# MO1.net
KiCad netlist of a schematic drawn in EAGLE
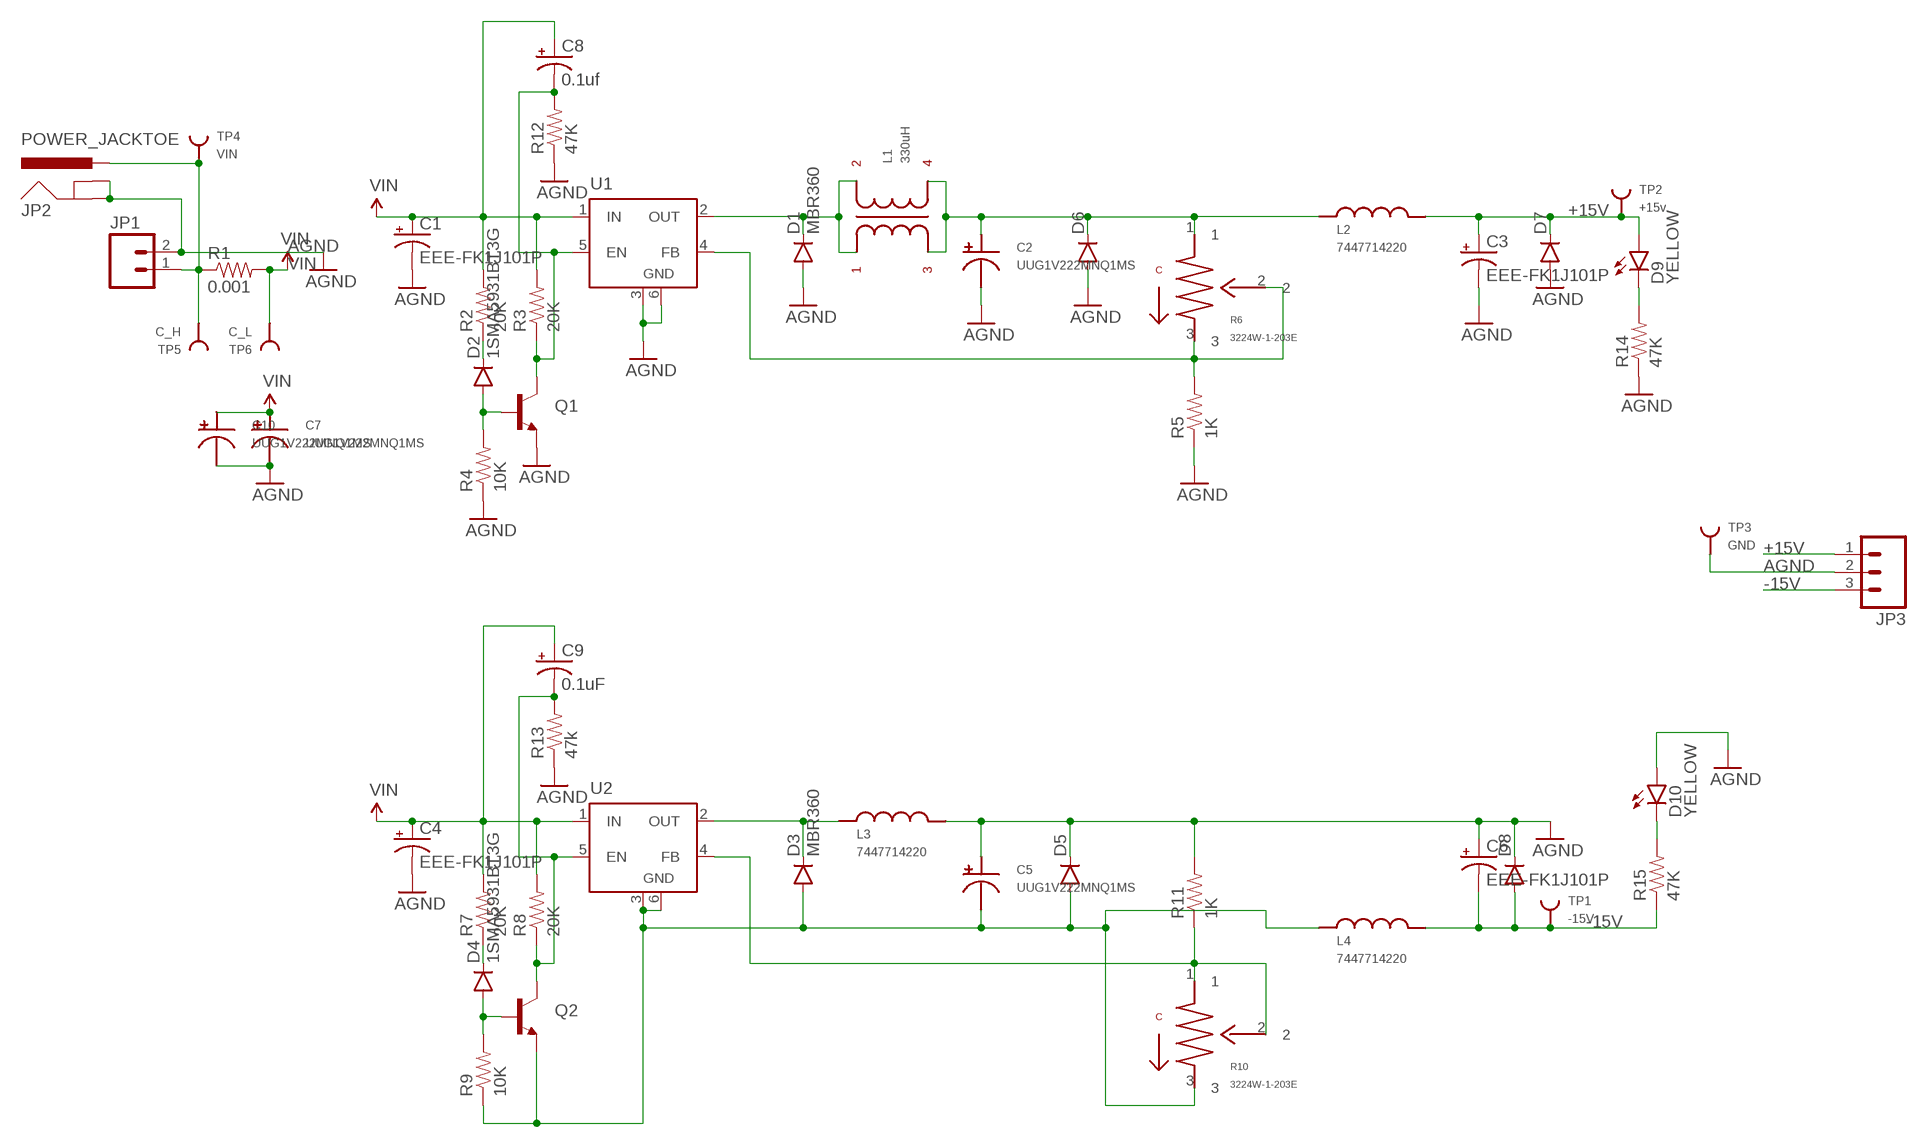
[diagram p0: schematic, sheet 1]

(export (version "E")
  (design (tool "Eeschema 10.0.6"))
  (components
    (comp (ref "C1")
      (value "EEE-FK1J101P")
      (footprint "eagle-import:PANASONIC_G")
      (libsource (lib "eagle-import") (part "CAP_POLG"))
    )
    (comp (ref "C2")
      (value "UUG1V222MNQ1MS")
      (footprint "eagle-import:POL_18X21.5")
      (libsource (lib "eagle-import") (part "UUG1V222MNQ1MS"))
    )
    (comp (ref "C3")
      (value "EEE-FK1J101P")
      (footprint "eagle-import:PANASONIC_G")
      (libsource (lib "eagle-import") (part "CAP_POLG"))
    )
    (comp (ref "C4")
      (value "EEE-FK1J101P")
      (footprint "eagle-import:PANASONIC_G")
      (libsource (lib "eagle-import") (part "CAP_POLG"))
    )
    (comp (ref "C5")
      (value "UUG1V222MNQ1MS")
      (footprint "eagle-import:POL_18X21.5")
      (libsource (lib "eagle-import") (part "UUG1V222MNQ1MS"))
    )
    (comp (ref "C6")
      (value "EEE-FK1J101P")
      (footprint "eagle-import:PANASONIC_G")
      (libsource (lib "eagle-import") (part "CAP_POLG"))
    )
    (comp (ref "C7")
      (value "UUG1V222MNQ1MS")
      (footprint "eagle-import:POL_18X21.5")
      (libsource (lib "eagle-import") (part "UUG1V222MNQ1MS"))
    )
    (comp (ref "C8")
      (value "0.1uf")
      (footprint "eagle-import:PANASONIC_C")
      (libsource (lib "eagle-import") (part "CAP_POLC"))
    )
    (comp (ref "C9")
      (value "0.1uF")
      (footprint "eagle-import:PANASONIC_C")
      (libsource (lib "eagle-import") (part "CAP_POLC"))
    )
    (comp (ref "C10")
      (value "UUG1V222MNQ1MS")
      (footprint "eagle-import:POL_18X21.5")
      (libsource (lib "eagle-import") (part "UUG1V222MNQ1MS"))
    )
    (comp (ref "D1")
      (value "MBR360")
      (footprint "eagle-import:SMB-DIODE")
      (libsource (lib "eagle-import") (part "DIODESMB"))
    )
    (comp (ref "D2")
      (value "1SMA5931BT3G")
      (footprint "eagle-import:SMA-DIODE")
      (libsource (lib "eagle-import") (part "DIODESMA"))
    )
    (comp (ref "D3")
      (value "MBR360")
      (footprint "eagle-import:SMB-DIODE")
      (libsource (lib "eagle-import") (part "DIODESMB"))
    )
    (comp (ref "D4")
      (value "1SMA5931BT3G")
      (footprint "eagle-import:SMA-DIODE")
      (libsource (lib "eagle-import") (part "DIODESMA"))
    )
    (comp (ref "D5")
      (value "DIODESMA")
      (footprint "eagle-import:SMA-DIODE")
      (libsource (lib "eagle-import") (part "DIODESMA"))
    )
    (comp (ref "D6")
      (value "DIODESMA")
      (footprint "eagle-import:SMA-DIODE")
      (libsource (lib "eagle-import") (part "DIODESMA"))
    )
    (comp (ref "D7")
      (value "DIODESMA")
      (footprint "eagle-import:SMA-DIODE")
      (libsource (lib "eagle-import") (part "DIODESMA"))
    )
    (comp (ref "D8")
      (value "DIODESMA")
      (footprint "eagle-import:SMA-DIODE")
      (libsource (lib "eagle-import") (part "DIODESMA"))
    )
    (comp (ref "D9")
      (value "YELLOW")
      (footprint "eagle-import:LED-1206")
      (libsource (lib "eagle-import") (part "LED-YELLOW1206"))
    )
    (comp (ref "D10")
      (value "YELLOW")
      (footprint "eagle-import:LED-1206")
      (libsource (lib "eagle-import") (part "LED-YELLOW1206"))
    )
    (comp (ref "JP1")
      (value "M023.5MM_LOCK")
      (footprint "eagle-import:SCREWTERMINAL-3.5MM-2_LOCK")
      (libsource (lib "eagle-import") (part "M023.5MM_LOCK"))
    )
    (comp (ref "JP2")
      (value "POWER_JACKTOE")
      (footprint "eagle-import:POWER_JACK_SMD_OVERPASTE_TOE")
      (libsource (lib "eagle-import") (part "POWER_JACKTOE"))
    )
    (comp (ref "JP3")
      (value "M03SCREW_LOCK")
      (footprint "eagle-import:SCREWTERMINAL-3.5MM-3_LOCK.007S")
      (libsource (lib "eagle-import") (part "M03SCREW_LOCK"))
    )
    (comp (ref "L1")
      (value "330uH")
      (footprint "eagle-import:DRQ127")
      (libsource (lib "eagle-import") (part "DRQ127-331-R"))
    )
    (comp (ref "L2")
      (value "7447714220")
      (footprint "eagle-import:INDUCTOR_10X10")
      (libsource (lib "eagle-import") (part "7447714220"))
    )
    (comp (ref "L3")
      (value "7447714220")
      (footprint "eagle-import:INDUCTOR_10X10")
      (libsource (lib "eagle-import") (part "7447714220"))
    )
    (comp (ref "L4")
      (value "7447714220")
      (footprint "eagle-import:INDUCTOR_10X10")
      (libsource (lib "eagle-import") (part "7447714220"))
    )
    (comp (ref "Q1")
      (value "TRANSISTOR_NPNSOT23-3")
      (footprint "eagle-import:SOT23-3")
      (libsource (lib "eagle-import") (part "TRANSISTOR_NPNSOT23-3"))
    )
    (comp (ref "Q2")
      (value "TRANSISTOR_NPNSOT23-3")
      (footprint "eagle-import:SOT23-3")
      (libsource (lib "eagle-import") (part "TRANSISTOR_NPNSOT23-3"))
    )
    (comp (ref "R1")
      (value "0.001")
      (footprint "eagle-import:2512")
      (libsource (lib "eagle-import") (part "0.001OHM-3W-1%(2512)3W/1%"))
    )
    (comp (ref "R2")
      (value "20K")
      (footprint "eagle-import:0603-RES")
      (libsource (lib "eagle-import") (part "1.8KOHM1/10W1%(0603)"))
    )
    (comp (ref "R3")
      (value "20K")
      (footprint "eagle-import:0603-RES")
      (libsource (lib "eagle-import") (part "1.8KOHM1/10W1%(0603)"))
    )
    (comp (ref "R4")
      (value "10K")
      (footprint "eagle-import:0603-RES")
      (libsource (lib "eagle-import") (part "1.8KOHM1/10W1%(0603)"))
    )
    (comp (ref "R5")
      (value "1K")
      (footprint "eagle-import:0805")
      (libsource (lib "eagle-import") (part "0.75OHM-1/4W-1%(0805)"))
    )
    (comp (ref "R6")
      (value "3224W-1-203E")
      (footprint "eagle-import:3224W")
      (libsource (lib "eagle-import") (part "3224W-1-203E"))
    )
    (comp (ref "R7")
      (value "20K")
      (footprint "eagle-import:0603-RES")
      (libsource (lib "eagle-import") (part "1.8KOHM1/10W1%(0603)"))
    )
    (comp (ref "R8")
      (value "20K")
      (footprint "eagle-import:0603-RES")
      (libsource (lib "eagle-import") (part "1.8KOHM1/10W1%(0603)"))
    )
    (comp (ref "R9")
      (value "10K")
      (footprint "eagle-import:0603-RES")
      (libsource (lib "eagle-import") (part "1.8KOHM1/10W1%(0603)"))
    )
    (comp (ref "R10")
      (value "3224W-1-203E")
      (footprint "eagle-import:3224W")
      (libsource (lib "eagle-import") (part "3224W-1-203E"))
    )
    (comp (ref "R11")
      (value "1K")
      (footprint "eagle-import:0805")
      (libsource (lib "eagle-import") (part "0.75OHM-1/4W-1%(0805)"))
    )
    (comp (ref "R12")
      (value "47K")
      (footprint "eagle-import:0603-RES")
      (libsource (lib "eagle-import") (part "1.8KOHM1/10W1%(0603)"))
    )
    (comp (ref "R13")
      (value "47k")
      (footprint "eagle-import:0603-RES")
      (libsource (lib "eagle-import") (part "1.8KOHM1/10W1%(0603)"))
    )
    (comp (ref "R14")
      (value "47K")
      (footprint "eagle-import:0603-RES")
      (libsource (lib "eagle-import") (part "1.8KOHM1/10W1%(0603)"))
    )
    (comp (ref "R15")
      (value "47K")
      (footprint "eagle-import:0603-RES")
      (libsource (lib "eagle-import") (part "1.8KOHM1/10W1%(0603)"))
    )
    (comp (ref "TP1")
      (value "-15V")
      (footprint "eagle-import:TP")
      (libsource (lib "eagle-import") (part "TP"))
    )
    (comp (ref "TP2")
      (value "+15v")
      (footprint "eagle-import:TP")
      (libsource (lib "eagle-import") (part "TP"))
    )
    (comp (ref "TP3")
      (value "GND")
      (footprint "eagle-import:TP")
      (libsource (lib "eagle-import") (part "TP"))
    )
    (comp (ref "TP4")
      (value "VIN")
      (footprint "eagle-import:TP")
      (libsource (lib "eagle-import") (part "TP"))
    )
    (comp (ref "TP5")
      (value "C_H")
      (footprint "eagle-import:TP")
      (libsource (lib "eagle-import") (part "TP"))
    )
    (comp (ref "TP6")
      (value "C_L")
      (footprint "eagle-import:TP")
      (libsource (lib "eagle-import") (part "TP"))
    )
    (comp (ref "U1")
      (value "LM2596S")
      (footprint "eagle-import:TO263-5")
      (libsource (lib "eagle-import") (part "LM2596S"))
    )
    (comp (ref "U2")
      (value "LM2596S")
      (footprint "eagle-import:TO263-5")
      (libsource (lib "eagle-import") (part "LM2596S"))
    )
  )
  (nets
    (net (code "1") (name "/+15V") (class "Default")
      (node (ref "C3") (pin "+") (pinfunction "+_+") (pintype "passive"))
      (node (ref "D7") (pin "C") (pinfunction "C_C") (pintype "passive"))
      (node (ref "D9") (pin "A") (pinfunction "A_A") (pintype "passive"))
      (node (ref "JP3") (pin "1") (pinfunction "1_1") (pintype "passive"))
      (node (ref "L2") (pin "2") (pinfunction "2_2") (pintype "bidirectional"))
      (node (ref "TP2") (pin "P$1") (pinfunction "TP_P$1") (pintype "bidirectional"))
    )
    (net (code "2") (name "/-15V") (class "Default")
      (node (ref "C6") (pin "-") (pinfunction "-_-") (pintype "passive"))
      (node (ref "D8") (pin "A") (pinfunction "A_A") (pintype "passive"))
      (node (ref "JP3") (pin "3") (pinfunction "3_3") (pintype "passive"))
      (node (ref "L4") (pin "2") (pinfunction "2_2") (pintype "bidirectional"))
      (node (ref "R15") (pin "1") (pinfunction "1_1") (pintype "passive"))
      (node (ref "TP1") (pin "P$1") (pinfunction "TP_P$1") (pintype "bidirectional"))
    )
    (net (code "3") (name "AGND") (class "Default")
      (node (ref "C1") (pin "-") (pinfunction "-_-") (pintype "passive"))
      (node (ref "C10") (pin "NEGATIVE") (pinfunction "NEGATIVE_NEGATIVE") (pintype "bidirectional"))
      (node (ref "C2") (pin "NEGATIVE") (pinfunction "NEGATIVE_NEGATIVE") (pintype "bidirectional"))
      (node (ref "C3") (pin "-") (pinfunction "-_-") (pintype "passive"))
      (node (ref "C4") (pin "-") (pinfunction "-_-") (pintype "passive"))
      (node (ref "C5") (pin "POSITIVE") (pinfunction "POSITIVE_POSITIVE") (pintype "bidirectional"))
      (node (ref "C6") (pin "+") (pinfunction "+_+") (pintype "passive"))
      (node (ref "C7") (pin "NEGATIVE") (pinfunction "NEGATIVE_NEGATIVE") (pintype "bidirectional"))
      (node (ref "D1") (pin "A") (pinfunction "A_A") (pintype "passive"))
      (node (ref "D10") (pin "A") (pinfunction "A_A") (pintype "passive"))
      (node (ref "D5") (pin "C") (pinfunction "C_C") (pintype "passive"))
      (node (ref "D6") (pin "A") (pinfunction "A_A") (pintype "passive"))
      (node (ref "D7") (pin "A") (pinfunction "A_A") (pintype "passive"))
      (node (ref "D8") (pin "C") (pinfunction "C_C") (pintype "passive"))
      (node (ref "JP1") (pin "2") (pinfunction "2_2") (pintype "passive"))
      (node (ref "JP2") (pin "GND") (pinfunction "GNDBREAK_GND") (pintype "bidirectional"))
      (node (ref "JP2") (pin "P$4") (pinfunction "GND_P$4") (pintype "bidirectional"))
      (node (ref "JP3") (pin "2") (pinfunction "2_2") (pintype "passive"))
      (node (ref "L3") (pin "2") (pinfunction "2_2") (pintype "bidirectional"))
      (node (ref "Q1") (pin "2") (pinfunction "E_2") (pintype "passive"))
      (node (ref "R11") (pin "2") (pinfunction "2_2") (pintype "passive"))
      (node (ref "R12") (pin "1") (pinfunction "1_1") (pintype "passive"))
      (node (ref "R13") (pin "1") (pinfunction "1_1") (pintype "passive"))
      (node (ref "R14") (pin "1") (pinfunction "1_1") (pintype "passive"))
      (node (ref "R4") (pin "1") (pinfunction "1_1") (pintype "passive"))
      (node (ref "R5") (pin "1") (pinfunction "1_1") (pintype "passive"))
      (node (ref "TP3") (pin "P$1") (pinfunction "TP_P$1") (pintype "bidirectional"))
      (node (ref "U1") (pin "3") (pinfunction "GND_3") (pintype "power_in"))
      (node (ref "U1") (pin "6") (pinfunction "GND_6") (pintype "power_in"))
    )
    (net (code "4") (name "Net-(C2-PadPOSITIVE)") (class "Default")
      (node (ref "C2") (pin "POSITIVE") (pinfunction "POSITIVE_POSITIVE") (pintype "bidirectional"))
      (node (ref "D6") (pin "C") (pinfunction "C_C") (pintype "passive"))
      (node (ref "L1") (pin "3") (pinfunction "3_3") (pintype "bidirectional"))
      (node (ref "L1") (pin "4") (pinfunction "4_4") (pintype "bidirectional"))
      (node (ref "L2") (pin "1") (pinfunction "1_1") (pintype "bidirectional"))
      (node (ref "R6") (pin "1") (pinfunction "1_1") (pintype "bidirectional"))
    )
    (net (code "5") (name "Net-(D2-PadC)") (class "Default")
      (node (ref "D2") (pin "C") (pinfunction "C_C") (pintype "passive"))
      (node (ref "R2") (pin "1") (pinfunction "1_1") (pintype "passive"))
    )
    (net (code "6") (name "Net-(D4-PadC)") (class "Default")
      (node (ref "D4") (pin "C") (pinfunction "C_C") (pintype "passive"))
      (node (ref "R7") (pin "1") (pinfunction "1_1") (pintype "passive"))
    )
    (net (code "7") (name "Net-(D9-PadC)") (class "Default")
      (node (ref "D9") (pin "C") (pinfunction "C_C") (pintype "passive"))
      (node (ref "R14") (pin "2") (pinfunction "2_2") (pintype "passive"))
    )
    (net (code "8") (name "Net-(D10-PadC)") (class "Default")
      (node (ref "D10") (pin "C") (pinfunction "C_C") (pintype "passive"))
      (node (ref "R15") (pin "2") (pinfunction "2_2") (pintype "passive"))
    )
    (net (code "9") (name "Net-(JP2-PWR)") (class "Default")
      (node (ref "JP1") (pin "1") (pinfunction "1_1") (pintype "passive"))
      (node (ref "JP2") (pin "VIN0") (pinfunction "PWR_VIN0") (pintype "bidirectional"))
      (node (ref "R1") (pin "1") (pinfunction "1_1") (pintype "passive"))
      (node (ref "TP4") (pin "P$1") (pinfunction "TP_P$1") (pintype "bidirectional"))
      (node (ref "TP5") (pin "P$1") (pinfunction "TP_P$1") (pintype "bidirectional"))
    )
    (net (code "10") (name "Net-(Q1-B)") (class "Default")
      (node (ref "D2") (pin "A") (pinfunction "A_A") (pintype "passive"))
      (node (ref "Q1") (pin "1") (pinfunction "B_1") (pintype "passive"))
      (node (ref "R4") (pin "2") (pinfunction "2_2") (pintype "passive"))
    )
    (net (code "11") (name "Net-(Q1-C)") (class "Default")
      (node (ref "C8") (pin "-") (pinfunction "-_-") (pintype "passive"))
      (node (ref "Q1") (pin "3") (pinfunction "C_3") (pintype "passive"))
      (node (ref "R12") (pin "2") (pinfunction "2_2") (pintype "passive"))
      (node (ref "R3") (pin "1") (pinfunction "1_1") (pintype "passive"))
      (node (ref "U1") (pin "5") (pinfunction "EN_5") (pintype "input"))
    )
    (net (code "12") (name "Net-(Q2-B)") (class "Default")
      (node (ref "D4") (pin "A") (pinfunction "A_A") (pintype "passive"))
      (node (ref "Q2") (pin "1") (pinfunction "B_1") (pintype "passive"))
      (node (ref "R9") (pin "2") (pinfunction "2_2") (pintype "passive"))
    )
    (net (code "13") (name "Net-(Q2-C)") (class "Default")
      (node (ref "C9") (pin "-") (pinfunction "-_-") (pintype "passive"))
      (node (ref "Q2") (pin "3") (pinfunction "C_3") (pintype "passive"))
      (node (ref "R13") (pin "2") (pinfunction "2_2") (pintype "passive"))
      (node (ref "R8") (pin "1") (pinfunction "1_1") (pintype "passive"))
      (node (ref "U2") (pin "5") (pinfunction "EN_5") (pintype "input"))
    )
    (net (code "14") (name "Net-(Q2-E)") (class "Default")
      (node (ref "C5") (pin "NEGATIVE") (pinfunction "NEGATIVE_NEGATIVE") (pintype "bidirectional"))
      (node (ref "D3") (pin "A") (pinfunction "A_A") (pintype "passive"))
      (node (ref "D5") (pin "A") (pinfunction "A_A") (pintype "passive"))
      (node (ref "L4") (pin "1") (pinfunction "1_1") (pintype "bidirectional"))
      (node (ref "Q2") (pin "2") (pinfunction "E_2") (pintype "passive"))
      (node (ref "R10") (pin "3") (pinfunction "3_3") (pintype "bidirectional"))
      (node (ref "R9") (pin "1") (pinfunction "1_1") (pintype "passive"))
      (node (ref "U2") (pin "3") (pinfunction "GND_3") (pintype "power_in"))
      (node (ref "U2") (pin "6") (pinfunction "GND_6") (pintype "power_in"))
    )
    (net (code "15") (name "Net-(U1-FB)") (class "Default")
      (node (ref "R5") (pin "2") (pinfunction "2_2") (pintype "passive"))
      (node (ref "R6") (pin "2") (pinfunction "2_2") (pintype "bidirectional"))
      (node (ref "R6") (pin "3") (pinfunction "3_3") (pintype "bidirectional"))
      (node (ref "U1") (pin "4") (pinfunction "FB_4") (pintype "input"))
    )
    (net (code "16") (name "Net-(U1-OUT)") (class "Default")
      (node (ref "D1") (pin "C") (pinfunction "C_C") (pintype "passive"))
      (node (ref "L1") (pin "1") (pinfunction "1_1") (pintype "bidirectional"))
      (node (ref "L1") (pin "2") (pinfunction "2_2") (pintype "bidirectional"))
      (node (ref "U1") (pin "2") (pinfunction "OUT_2") (pintype "output"))
    )
    (net (code "17") (name "Net-(U2-FB)") (class "Default")
      (node (ref "R10") (pin "1") (pinfunction "1_1") (pintype "bidirectional"))
      (node (ref "R10") (pin "2") (pinfunction "2_2") (pintype "bidirectional"))
      (node (ref "R11") (pin "1") (pinfunction "1_1") (pintype "passive"))
      (node (ref "U2") (pin "4") (pinfunction "FB_4") (pintype "input"))
    )
    (net (code "18") (name "Net-(U2-OUT)") (class "Default")
      (node (ref "D3") (pin "C") (pinfunction "C_C") (pintype "passive"))
      (node (ref "L3") (pin "1") (pinfunction "1_1") (pintype "bidirectional"))
      (node (ref "U2") (pin "2") (pinfunction "OUT_2") (pintype "output"))
    )
    (net (code "19") (name "VIN") (class "Default")
      (node (ref "C1") (pin "+") (pinfunction "+_+") (pintype "passive"))
      (node (ref "C10") (pin "POSITIVE") (pinfunction "POSITIVE_POSITIVE") (pintype "bidirectional"))
      (node (ref "C4") (pin "+") (pinfunction "+_+") (pintype "passive"))
      (node (ref "C7") (pin "POSITIVE") (pinfunction "POSITIVE_POSITIVE") (pintype "bidirectional"))
      (node (ref "C8") (pin "+") (pinfunction "+_+") (pintype "passive"))
      (node (ref "C9") (pin "+") (pinfunction "+_+") (pintype "passive"))
      (node (ref "R1") (pin "2") (pinfunction "2_2") (pintype "passive"))
      (node (ref "R2") (pin "2") (pinfunction "2_2") (pintype "passive"))
      (node (ref "R3") (pin "2") (pinfunction "2_2") (pintype "passive"))
      (node (ref "R7") (pin "2") (pinfunction "2_2") (pintype "passive"))
      (node (ref "R8") (pin "2") (pinfunction "2_2") (pintype "passive"))
      (node (ref "TP6") (pin "P$1") (pinfunction "TP_P$1") (pintype "bidirectional"))
      (node (ref "U1") (pin "1") (pinfunction "IN_1") (pintype "input"))
      (node (ref "U2") (pin "1") (pinfunction "IN_1") (pintype "input"))
    )
  )
)
